# interface.net
KiCad netlist of a schematic drawn in Altium Designer
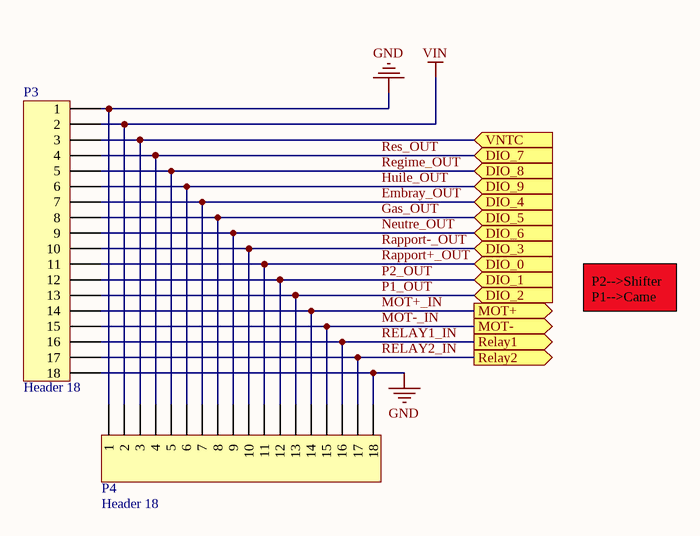
[diagram p0: interface.SchDoc]

(export (version "E")
  (design (tool "Eeschema 10.0.6"))
  (components
    (comp (ref "P3")
      (value "Header 18")
      (footprint "PHOENIX_PTSA05_18")
      (description "Header, 10-Pin")
      (fields
        (field (name "MANUFACTURER PARTNUM") "1990164")
        (field (name "MANUFACTURER") "Phoenix")
        (field (name "PUBLISHER") "Altium Limited")
      )
      (libsource (lib "Sch_GB_lib") (part "Header 18"))
    )
    (comp (ref "P4")
      (value "Header 18")
      (footprint "HDR1X18")
      (description "Header, 10-Pin")
      (fields (field (name "PUBLISHER") "Altium Limited"))
      (libsource (lib "") (part "Header 18_1"))
    )
  )
  (nets
    (net (code "1") (name "/Embray_OUT") (class "Default")
      (node (ref "P3") (pin "7") (pinfunction "7_7") (pintype "passive"))
      (node (ref "P4") (pin "7") (pinfunction "7_7") (pintype "passive"))
    )
    (net (code "2") (name "/Gas_OUT") (class "Default")
      (node (ref "P3") (pin "8") (pinfunction "8_8") (pintype "passive"))
      (node (ref "P4") (pin "8") (pinfunction "8_8") (pintype "passive"))
    )
    (net (code "3") (name "/Huile_OUT") (class "Default")
      (node (ref "P3") (pin "6") (pinfunction "6_6") (pintype "passive"))
      (node (ref "P4") (pin "6") (pinfunction "6_6") (pintype "passive"))
    )
    (net (code "4") (name "/MOT+_IN") (class "Default")
      (node (ref "P3") (pin "14") (pinfunction "14_14") (pintype "passive"))
      (node (ref "P4") (pin "14") (pinfunction "14_14") (pintype "passive"))
    )
    (net (code "5") (name "/MOT-_IN") (class "Default")
      (node (ref "P3") (pin "15") (pinfunction "15_15") (pintype "passive"))
      (node (ref "P4") (pin "15") (pinfunction "15_15") (pintype "passive"))
    )
    (net (code "6") (name "/Neutre_OUT") (class "Default")
      (node (ref "P3") (pin "9") (pinfunction "9_9") (pintype "passive"))
      (node (ref "P4") (pin "9") (pinfunction "9_9") (pintype "passive"))
    )
    (net (code "7") (name "/P1_OUT") (class "Default")
      (node (ref "P3") (pin "13") (pinfunction "13_13") (pintype "passive"))
      (node (ref "P4") (pin "13") (pinfunction "13_13") (pintype "passive"))
    )
    (net (code "8") (name "/P2_OUT") (class "Default")
      (node (ref "P3") (pin "12") (pinfunction "12_12") (pintype "passive"))
      (node (ref "P4") (pin "12") (pinfunction "12_12") (pintype "passive"))
    )
    (net (code "9") (name "/RELAY1_IN") (class "Default")
      (node (ref "P3") (pin "16") (pinfunction "16_16") (pintype "passive"))
      (node (ref "P4") (pin "16") (pinfunction "16_16") (pintype "passive"))
    )
    (net (code "10") (name "/RELAY2_IN") (class "Default")
      (node (ref "P3") (pin "17") (pinfunction "17_17") (pintype "passive"))
      (node (ref "P4") (pin "17") (pinfunction "17_17") (pintype "passive"))
    )
    (net (code "11") (name "/Rapport+_OUT") (class "Default")
      (node (ref "P3") (pin "11") (pinfunction "11_11") (pintype "passive"))
      (node (ref "P4") (pin "11") (pinfunction "11_11") (pintype "passive"))
    )
    (net (code "12") (name "/Rapport-_OUT") (class "Default")
      (node (ref "P3") (pin "10") (pinfunction "10_10") (pintype "passive"))
      (node (ref "P4") (pin "10") (pinfunction "10_10") (pintype "passive"))
    )
    (net (code "13") (name "/Regime_OUT") (class "Default")
      (node (ref "P3") (pin "5") (pinfunction "5_5") (pintype "passive"))
      (node (ref "P4") (pin "5") (pinfunction "5_5") (pintype "passive"))
    )
    (net (code "14") (name "/Res_OUT") (class "Default")
      (node (ref "P3") (pin "4") (pinfunction "4_4") (pintype "passive"))
      (node (ref "P4") (pin "4") (pinfunction "4_4") (pintype "passive"))
    )
    (net (code "15") (name "/VNTC") (class "Default")
      (node (ref "P3") (pin "3") (pinfunction "3_3") (pintype "passive"))
      (node (ref "P4") (pin "3") (pinfunction "3_3") (pintype "passive"))
    )
    (net (code "16") (name "GND") (class "Default")
      (node (ref "P3") (pin "1") (pinfunction "1_1") (pintype "passive"))
      (node (ref "P3") (pin "18") (pinfunction "18_18") (pintype "passive"))
      (node (ref "P4") (pin "1") (pinfunction "1_1") (pintype "passive"))
      (node (ref "P4") (pin "18") (pinfunction "18_18") (pintype "passive"))
    )
    (net (code "17") (name "VIN") (class "Default")
      (node (ref "P3") (pin "2") (pinfunction "2_2") (pintype "passive"))
      (node (ref "P4") (pin "2") (pinfunction "2_2") (pintype "passive"))
    )
  )
)
